# arduino_due_connection.net
KiCad netlist of a schematic drawn in Altium Designer
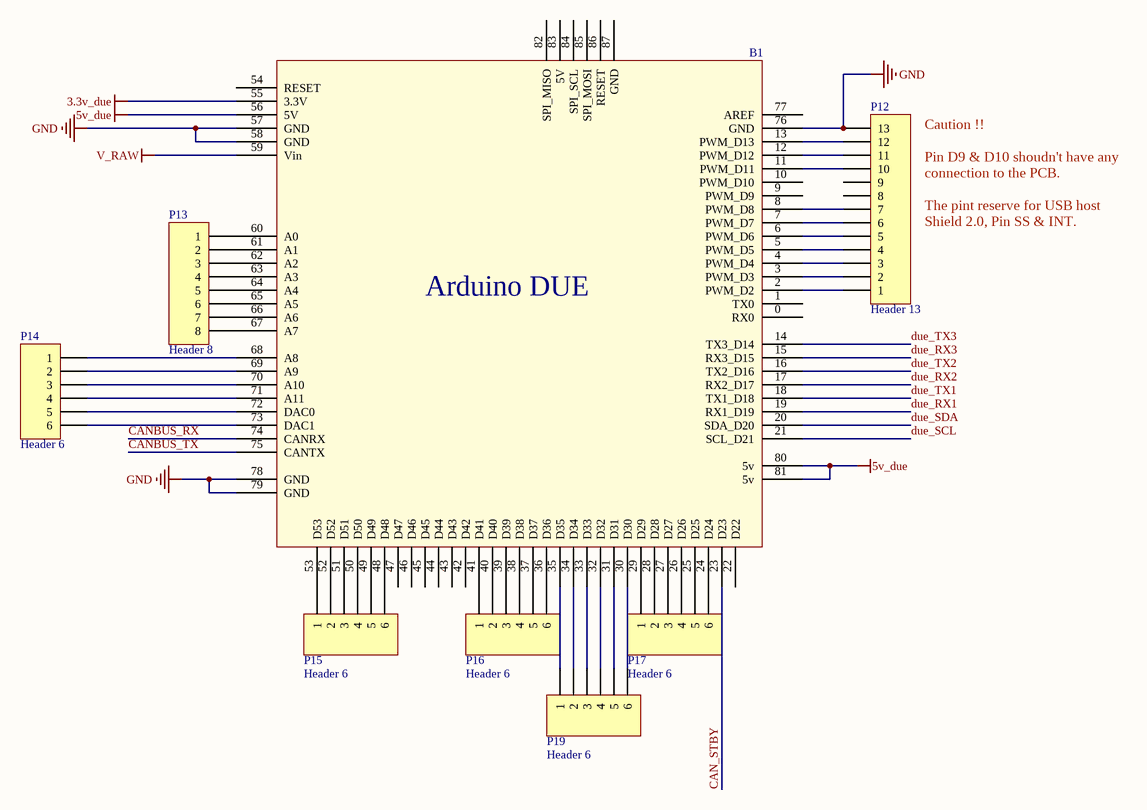
[diagram p0: arduino due connection.SchDoc]

(export (version "E")
  (design (tool "Eeschema 10.0.6"))
  (components
    (comp (ref "B1")
      (value "Arduino due")
      (footprint "arduino_due_pinmap_v3")
      (libsource (lib "arduino due") (part "arduino due"))
    )
    (comp (ref "P12")
      (value "Header 13")
      (footprint "HDR1X13")
      (description "Header, 13-Pin")
      (fields (field (name "PUBLISHER") "Altium Limited"))
      (libsource (lib "Miscellaneous Connectors") (part "Header 13"))
    )
    (comp (ref "P13")
      (value "Header 8")
      (footprint "HDR1X8")
      (description "Header, 8-Pin")
      (fields (field (name "PUBLISHER") "Altium Limited"))
      (libsource (lib "Miscellaneous Connectors") (part "Header 8"))
    )
    (comp (ref "P14")
      (value "Header 6")
      (footprint "HDR1X6")
      (description "Header, 6-Pin")
      (fields (field (name "PUBLISHER") "Altium Limited"))
      (libsource (lib "Miscellaneous Connectors") (part "Header 6"))
    )
    (comp (ref "P15")
      (value "Header 6")
      (footprint "HDR1X6")
      (description "Header, 6-Pin")
      (fields (field (name "PUBLISHER") "Altium Limited"))
      (libsource (lib "") (part "Header 6_1"))
    )
    (comp (ref "P16")
      (value "Header 6")
      (footprint "HDR1X6")
      (description "Header, 6-Pin")
      (fields (field (name "PUBLISHER") "Altium Limited"))
      (libsource (lib "") (part "Header 6_1"))
    )
    (comp (ref "P17")
      (value "Header 6")
      (footprint "HDR1X6")
      (description "Header, 6-Pin")
      (fields (field (name "PUBLISHER") "Altium Limited"))
      (libsource (lib "") (part "Header 6_1"))
    )
    (comp (ref "P19")
      (value "Header 6")
      (footprint "HDR1X6")
      (description "Header, 6-Pin")
      (fields (field (name "PUBLISHER") "Altium Limited"))
      (libsource (lib "") (part "Header 6_1"))
    )
  )
  (nets
    (net (code "1") (name "/CANBUS_RX") (class "Default")
      (node (ref "B1") (pin "74") (pinfunction "CANRX_74") (pintype "passive"))
    )
    (net (code "2") (name "/CANBUS_TX") (class "Default")
      (node (ref "B1") (pin "75") (pinfunction "CANTX_75") (pintype "passive"))
    )
    (net (code "3") (name "/CAN_STBY") (class "Default")
      (node (ref "B1") (pin "23") (pinfunction "D23_23") (pintype "passive"))
    )
    (net (code "4") (name "/due_RX1") (class "Default")
      (node (ref "B1") (pin "19") (pinfunction "RX1_D19_19") (pintype "passive"))
    )
    (net (code "5") (name "/due_RX2") (class "Default")
      (node (ref "B1") (pin "17") (pinfunction "RX2_D17_17") (pintype "passive"))
    )
    (net (code "6") (name "/due_RX3") (class "Default")
      (node (ref "B1") (pin "15") (pinfunction "RX3_D15_15") (pintype "passive"))
    )
    (net (code "7") (name "/due_SCL") (class "Default")
      (node (ref "B1") (pin "21") (pinfunction "SCL_D21_21") (pintype "passive"))
    )
    (net (code "8") (name "/due_SDA") (class "Default")
      (node (ref "B1") (pin "20") (pinfunction "SDA_D20_20") (pintype "passive"))
    )
    (net (code "9") (name "/due_TX1") (class "Default")
      (node (ref "B1") (pin "18") (pinfunction "TX1_D18_18") (pintype "passive"))
    )
    (net (code "10") (name "/due_TX2") (class "Default")
      (node (ref "B1") (pin "16") (pinfunction "TX2_D16_16") (pintype "passive"))
    )
    (net (code "11") (name "/due_TX3") (class "Default")
      (node (ref "B1") (pin "14") (pinfunction "TX3_D14_14") (pintype "passive"))
    )
    (net (code "12") (name "3.3v_due") (class "Default")
      (node (ref "B1") (pin "55") (pinfunction "3.3V_55") (pintype "passive"))
    )
    (net (code "13") (name "5v_due") (class "Default")
      (node (ref "B1") (pin "56") (pinfunction "5V_56") (pintype "passive"))
      (node (ref "B1") (pin "80") (pinfunction "5v_80") (pintype "passive"))
      (node (ref "B1") (pin "81") (pinfunction "5v_81") (pintype "passive"))
    )
    (net (code "14") (name "GND") (class "Default")
      (node (ref "B1") (pin "57") (pinfunction "GND_57") (pintype "passive"))
      (node (ref "B1") (pin "58") (pinfunction "GND_58") (pintype "passive"))
      (node (ref "B1") (pin "76") (pinfunction "GND_76") (pintype "passive"))
      (node (ref "B1") (pin "78") (pinfunction "GND_78") (pintype "passive"))
      (node (ref "B1") (pin "79") (pinfunction "GND_79") (pintype "passive"))
      (node (ref "P12") (pin "13") (pinfunction "13_13") (pintype "passive"))
    )
    (net (code "15") (name "Net-(B1-A0)") (class "Default")
      (node (ref "B1") (pin "60") (pinfunction "A0_60") (pintype "passive"))
      (node (ref "P13") (pin "1") (pinfunction "1_1") (pintype "passive"))
    )
    (net (code "16") (name "Net-(B1-A1)") (class "Default")
      (node (ref "B1") (pin "61") (pinfunction "A1_61") (pintype "passive"))
      (node (ref "P13") (pin "2") (pinfunction "2_2") (pintype "passive"))
    )
    (net (code "17") (name "Net-(B1-A2)") (class "Default")
      (node (ref "B1") (pin "62") (pinfunction "A2_62") (pintype "passive"))
      (node (ref "P13") (pin "3") (pinfunction "3_3") (pintype "passive"))
    )
    (net (code "18") (name "Net-(B1-A3)") (class "Default")
      (node (ref "B1") (pin "63") (pinfunction "A3_63") (pintype "passive"))
      (node (ref "P13") (pin "4") (pinfunction "4_4") (pintype "passive"))
    )
    (net (code "19") (name "Net-(B1-A4)") (class "Default")
      (node (ref "B1") (pin "64") (pinfunction "A4_64") (pintype "passive"))
      (node (ref "P13") (pin "5") (pinfunction "5_5") (pintype "passive"))
    )
    (net (code "20") (name "Net-(B1-A5)") (class "Default")
      (node (ref "B1") (pin "65") (pinfunction "A5_65") (pintype "passive"))
      (node (ref "P13") (pin "6") (pinfunction "6_6") (pintype "passive"))
    )
    (net (code "21") (name "Net-(B1-A6)") (class "Default")
      (node (ref "B1") (pin "66") (pinfunction "A6_66") (pintype "passive"))
      (node (ref "P13") (pin "7") (pinfunction "7_7") (pintype "passive"))
    )
    (net (code "22") (name "Net-(B1-A7)") (class "Default")
      (node (ref "B1") (pin "67") (pinfunction "A7_67") (pintype "passive"))
      (node (ref "P13") (pin "8") (pinfunction "8_8") (pintype "passive"))
    )
    (net (code "23") (name "Net-(B1-A8)") (class "Default")
      (node (ref "B1") (pin "68") (pinfunction "A8_68") (pintype "passive"))
      (node (ref "P14") (pin "1") (pinfunction "1_1") (pintype "passive"))
    )
    (net (code "24") (name "Net-(B1-A9)") (class "Default")
      (node (ref "B1") (pin "69") (pinfunction "A9_69") (pintype "passive"))
      (node (ref "P14") (pin "2") (pinfunction "2_2") (pintype "passive"))
    )
    (net (code "25") (name "Net-(B1-A10)") (class "Default")
      (node (ref "B1") (pin "70") (pinfunction "A10_70") (pintype "passive"))
      (node (ref "P14") (pin "3") (pinfunction "3_3") (pintype "passive"))
    )
    (net (code "26") (name "Net-(B1-A11)") (class "Default")
      (node (ref "B1") (pin "71") (pinfunction "A11_71") (pintype "passive"))
      (node (ref "P14") (pin "4") (pinfunction "4_4") (pintype "passive"))
    )
    (net (code "27") (name "Net-(B1-D24)") (class "Default")
      (node (ref "B1") (pin "24") (pinfunction "D24_24") (pintype "passive"))
      (node (ref "P17") (pin "6") (pinfunction "6_6") (pintype "passive"))
    )
    (net (code "28") (name "Net-(B1-D25)") (class "Default")
      (node (ref "B1") (pin "25") (pinfunction "D25_25") (pintype "passive"))
      (node (ref "P17") (pin "5") (pinfunction "5_5") (pintype "passive"))
    )
    (net (code "29") (name "Net-(B1-D26)") (class "Default")
      (node (ref "B1") (pin "26") (pinfunction "D26_26") (pintype "passive"))
      (node (ref "P17") (pin "4") (pinfunction "4_4") (pintype "passive"))
    )
    (net (code "30") (name "Net-(B1-D27)") (class "Default")
      (node (ref "B1") (pin "27") (pinfunction "D27_27") (pintype "passive"))
      (node (ref "P17") (pin "3") (pinfunction "3_3") (pintype "passive"))
    )
    (net (code "31") (name "Net-(B1-D28)") (class "Default")
      (node (ref "B1") (pin "28") (pinfunction "D28_28") (pintype "passive"))
      (node (ref "P17") (pin "2") (pinfunction "2_2") (pintype "passive"))
    )
    (net (code "32") (name "Net-(B1-D29)") (class "Default")
      (node (ref "B1") (pin "29") (pinfunction "D29_29") (pintype "passive"))
      (node (ref "P17") (pin "1") (pinfunction "1_1") (pintype "passive"))
    )
    (net (code "33") (name "Net-(B1-D30)") (class "Default")
      (node (ref "B1") (pin "30") (pinfunction "D30_30") (pintype "passive"))
      (node (ref "P19") (pin "6") (pinfunction "6_6") (pintype "passive"))
    )
    (net (code "34") (name "Net-(B1-D31)") (class "Default")
      (node (ref "B1") (pin "31") (pinfunction "D31_31") (pintype "passive"))
      (node (ref "P19") (pin "5") (pinfunction "5_5") (pintype "passive"))
    )
    (net (code "35") (name "Net-(B1-D32)") (class "Default")
      (node (ref "B1") (pin "32") (pinfunction "D32_32") (pintype "passive"))
      (node (ref "P19") (pin "4") (pinfunction "4_4") (pintype "passive"))
    )
    (net (code "36") (name "Net-(B1-D33)") (class "Default")
      (node (ref "B1") (pin "33") (pinfunction "D33_33") (pintype "passive"))
      (node (ref "P19") (pin "3") (pinfunction "3_3") (pintype "passive"))
    )
    (net (code "37") (name "Net-(B1-D34)") (class "Default")
      (node (ref "B1") (pin "34") (pinfunction "D34_34") (pintype "passive"))
      (node (ref "P19") (pin "2") (pinfunction "2_2") (pintype "passive"))
    )
    (net (code "38") (name "Net-(B1-D35)") (class "Default")
      (node (ref "B1") (pin "35") (pinfunction "D35_35") (pintype "passive"))
      (node (ref "P19") (pin "1") (pinfunction "1_1") (pintype "passive"))
    )
    (net (code "39") (name "Net-(B1-D36)") (class "Default")
      (node (ref "B1") (pin "36") (pinfunction "D36_36") (pintype "passive"))
      (node (ref "P16") (pin "6") (pinfunction "6_6") (pintype "passive"))
    )
    (net (code "40") (name "Net-(B1-D37)") (class "Default")
      (node (ref "B1") (pin "37") (pinfunction "D37_37") (pintype "passive"))
      (node (ref "P16") (pin "5") (pinfunction "5_5") (pintype "passive"))
    )
    (net (code "41") (name "Net-(B1-D38)") (class "Default")
      (node (ref "B1") (pin "38") (pinfunction "D38_38") (pintype "passive"))
      (node (ref "P16") (pin "4") (pinfunction "4_4") (pintype "passive"))
    )
    (net (code "42") (name "Net-(B1-D39)") (class "Default")
      (node (ref "B1") (pin "39") (pinfunction "D39_39") (pintype "passive"))
      (node (ref "P16") (pin "3") (pinfunction "3_3") (pintype "passive"))
    )
    (net (code "43") (name "Net-(B1-D40)") (class "Default")
      (node (ref "B1") (pin "40") (pinfunction "D40_40") (pintype "passive"))
      (node (ref "P16") (pin "2") (pinfunction "2_2") (pintype "passive"))
    )
    (net (code "44") (name "Net-(B1-D41)") (class "Default")
      (node (ref "B1") (pin "41") (pinfunction "D41_41") (pintype "passive"))
      (node (ref "P16") (pin "1") (pinfunction "1_1") (pintype "passive"))
    )
    (net (code "45") (name "Net-(B1-D48)") (class "Default")
      (node (ref "B1") (pin "48") (pinfunction "D48_48") (pintype "passive"))
      (node (ref "P15") (pin "6") (pinfunction "6_6") (pintype "passive"))
    )
    (net (code "46") (name "Net-(B1-D49)") (class "Default")
      (node (ref "B1") (pin "49") (pinfunction "D49_49") (pintype "passive"))
      (node (ref "P15") (pin "5") (pinfunction "5_5") (pintype "passive"))
    )
    (net (code "47") (name "Net-(B1-D50)") (class "Default")
      (node (ref "B1") (pin "50") (pinfunction "D50_50") (pintype "passive"))
      (node (ref "P15") (pin "4") (pinfunction "4_4") (pintype "passive"))
    )
    (net (code "48") (name "Net-(B1-D51)") (class "Default")
      (node (ref "B1") (pin "51") (pinfunction "D51_51") (pintype "passive"))
      (node (ref "P15") (pin "3") (pinfunction "3_3") (pintype "passive"))
    )
    (net (code "49") (name "Net-(B1-D52)") (class "Default")
      (node (ref "B1") (pin "52") (pinfunction "D52_52") (pintype "passive"))
      (node (ref "P15") (pin "2") (pinfunction "2_2") (pintype "passive"))
    )
    (net (code "50") (name "Net-(B1-D53)") (class "Default")
      (node (ref "B1") (pin "53") (pinfunction "D53_53") (pintype "passive"))
      (node (ref "P15") (pin "1") (pinfunction "1_1") (pintype "passive"))
    )
    (net (code "51") (name "Net-(B1-DAC0)") (class "Default")
      (node (ref "B1") (pin "72") (pinfunction "DAC0_72") (pintype "passive"))
      (node (ref "P14") (pin "5") (pinfunction "5_5") (pintype "passive"))
    )
    (net (code "52") (name "Net-(B1-DAC1)") (class "Default")
      (node (ref "B1") (pin "73") (pinfunction "DAC1_73") (pintype "passive"))
      (node (ref "P14") (pin "6") (pinfunction "6_6") (pintype "passive"))
    )
    (net (code "53") (name "Net-(B1-PWM_D2)") (class "Default")
      (node (ref "B1") (pin "2") (pinfunction "PWM_D2_2") (pintype "passive"))
      (node (ref "P12") (pin "1") (pinfunction "1_1") (pintype "passive"))
    )
    (net (code "54") (name "Net-(B1-PWM_D3)") (class "Default")
      (node (ref "B1") (pin "3") (pinfunction "PWM_D3_3") (pintype "passive"))
      (node (ref "P12") (pin "2") (pinfunction "2_2") (pintype "passive"))
    )
    (net (code "55") (name "Net-(B1-PWM_D4)") (class "Default")
      (node (ref "B1") (pin "4") (pinfunction "PWM_D4_4") (pintype "passive"))
      (node (ref "P12") (pin "3") (pinfunction "3_3") (pintype "passive"))
    )
    (net (code "56") (name "Net-(B1-PWM_D5)") (class "Default")
      (node (ref "B1") (pin "5") (pinfunction "PWM_D5_5") (pintype "passive"))
      (node (ref "P12") (pin "4") (pinfunction "4_4") (pintype "passive"))
    )
    (net (code "57") (name "Net-(B1-PWM_D6)") (class "Default")
      (node (ref "B1") (pin "6") (pinfunction "PWM_D6_6") (pintype "passive"))
      (node (ref "P12") (pin "5") (pinfunction "5_5") (pintype "passive"))
    )
    (net (code "58") (name "Net-(B1-PWM_D7)") (class "Default")
      (node (ref "B1") (pin "7") (pinfunction "PWM_D7_7") (pintype "passive"))
      (node (ref "P12") (pin "6") (pinfunction "6_6") (pintype "passive"))
    )
    (net (code "59") (name "Net-(B1-PWM_D8)") (class "Default")
      (node (ref "B1") (pin "8") (pinfunction "PWM_D8_8") (pintype "passive"))
      (node (ref "P12") (pin "7") (pinfunction "7_7") (pintype "passive"))
    )
    (net (code "60") (name "Net-(B1-PWM_D11)") (class "Default")
      (node (ref "B1") (pin "11") (pinfunction "PWM_D11_11") (pintype "passive"))
      (node (ref "P12") (pin "10") (pinfunction "10_10") (pintype "passive"))
    )
    (net (code "61") (name "Net-(B1-PWM_D12)") (class "Default")
      (node (ref "B1") (pin "12") (pinfunction "PWM_D12_12") (pintype "passive"))
      (node (ref "P12") (pin "11") (pinfunction "11_11") (pintype "passive"))
    )
    (net (code "62") (name "Net-(B1-PWM_D13)") (class "Default")
      (node (ref "B1") (pin "13") (pinfunction "PWM_D13_13") (pintype "passive"))
      (node (ref "P12") (pin "12") (pinfunction "12_12") (pintype "passive"))
    )
    (net (code "63") (name "V_RAW") (class "Default")
      (node (ref "B1") (pin "59") (pinfunction "Vin_59") (pintype "passive"))
    )
    (net (code "64") (name "unconnected-(B1-5V-Pad83)") (class "Default")
      (node (ref "B1") (pin "83") (pinfunction "5V_83") (pintype "passive"))
    )
    (net (code "65") (name "unconnected-(B1-AREF-Pad77)") (class "Default")
      (node (ref "B1") (pin "77") (pinfunction "AREF_77") (pintype "passive"))
    )
    (net (code "66") (name "unconnected-(B1-D22-Pad22)") (class "Default")
      (node (ref "B1") (pin "22") (pinfunction "D22_22") (pintype "passive"))
    )
    (net (code "67") (name "unconnected-(B1-D42-Pad42)") (class "Default")
      (node (ref "B1") (pin "42") (pinfunction "D42_42") (pintype "passive"))
    )
    (net (code "68") (name "unconnected-(B1-D43-Pad43)") (class "Default")
      (node (ref "B1") (pin "43") (pinfunction "D43_43") (pintype "passive"))
    )
    (net (code "69") (name "unconnected-(B1-D44-Pad44)") (class "Default")
      (node (ref "B1") (pin "44") (pinfunction "D44_44") (pintype "passive"))
    )
    (net (code "70") (name "unconnected-(B1-D45-Pad45)") (class "Default")
      (node (ref "B1") (pin "45") (pinfunction "D45_45") (pintype "passive"))
    )
    (net (code "71") (name "unconnected-(B1-D46-Pad46)") (class "Default")
      (node (ref "B1") (pin "46") (pinfunction "D46_46") (pintype "passive"))
    )
    (net (code "72") (name "unconnected-(B1-D47-Pad47)") (class "Default")
      (node (ref "B1") (pin "47") (pinfunction "D47_47") (pintype "passive"))
    )
    (net (code "73") (name "unconnected-(B1-GND-Pad87)") (class "Default")
      (node (ref "B1") (pin "87") (pinfunction "GND_87") (pintype "passive"))
    )
    (net (code "74") (name "unconnected-(B1-PWM_D9-Pad9)") (class "Default")
      (node (ref "B1") (pin "9") (pinfunction "PWM_D9_9") (pintype "passive"))
    )
    (net (code "75") (name "unconnected-(B1-PWM_D10-Pad10)") (class "Default")
      (node (ref "B1") (pin "10") (pinfunction "PWM_D10_10") (pintype "passive"))
    )
    (net (code "76") (name "unconnected-(B1-RESET-Pad54)") (class "Default")
      (node (ref "B1") (pin "54") (pinfunction "RESET_54") (pintype "passive"))
    )
    (net (code "77") (name "unconnected-(B1-RESET-Pad86)") (class "Default")
      (node (ref "B1") (pin "86") (pinfunction "RESET_86") (pintype "passive"))
    )
    (net (code "78") (name "unconnected-(B1-RX0-Pad0)") (class "Default")
      (node (ref "B1") (pin "0") (pinfunction "RX0_0") (pintype "passive"))
    )
    (net (code "79") (name "unconnected-(B1-SPI_MISO-Pad82)") (class "Default")
      (node (ref "B1") (pin "82") (pinfunction "SPI_MISO_82") (pintype "passive"))
    )
    (net (code "80") (name "unconnected-(B1-SPI_MOSI-Pad85)") (class "Default")
      (node (ref "B1") (pin "85") (pinfunction "SPI_MOSI_85") (pintype "passive"))
    )
    (net (code "81") (name "unconnected-(B1-SPI_SCL-Pad84)") (class "Default")
      (node (ref "B1") (pin "84") (pinfunction "SPI_SCL_84") (pintype "passive"))
    )
    (net (code "82") (name "unconnected-(B1-TX0-Pad1)") (class "Default")
      (node (ref "B1") (pin "1") (pinfunction "TX0_1") (pintype "passive"))
    )
    (net (code "83") (name "unconnected-(P12-Pad8)") (class "Default")
      (node (ref "P12") (pin "8") (pinfunction "8_8") (pintype "passive"))
    )
    (net (code "84") (name "unconnected-(P12-Pad9)") (class "Default")
      (node (ref "P12") (pin "9") (pinfunction "9_9") (pintype "passive"))
    )
  )
)
